# STorM32_NT_imu_v211_mini-mpu9250.net
KiCad netlist of a schematic drawn in EAGLE
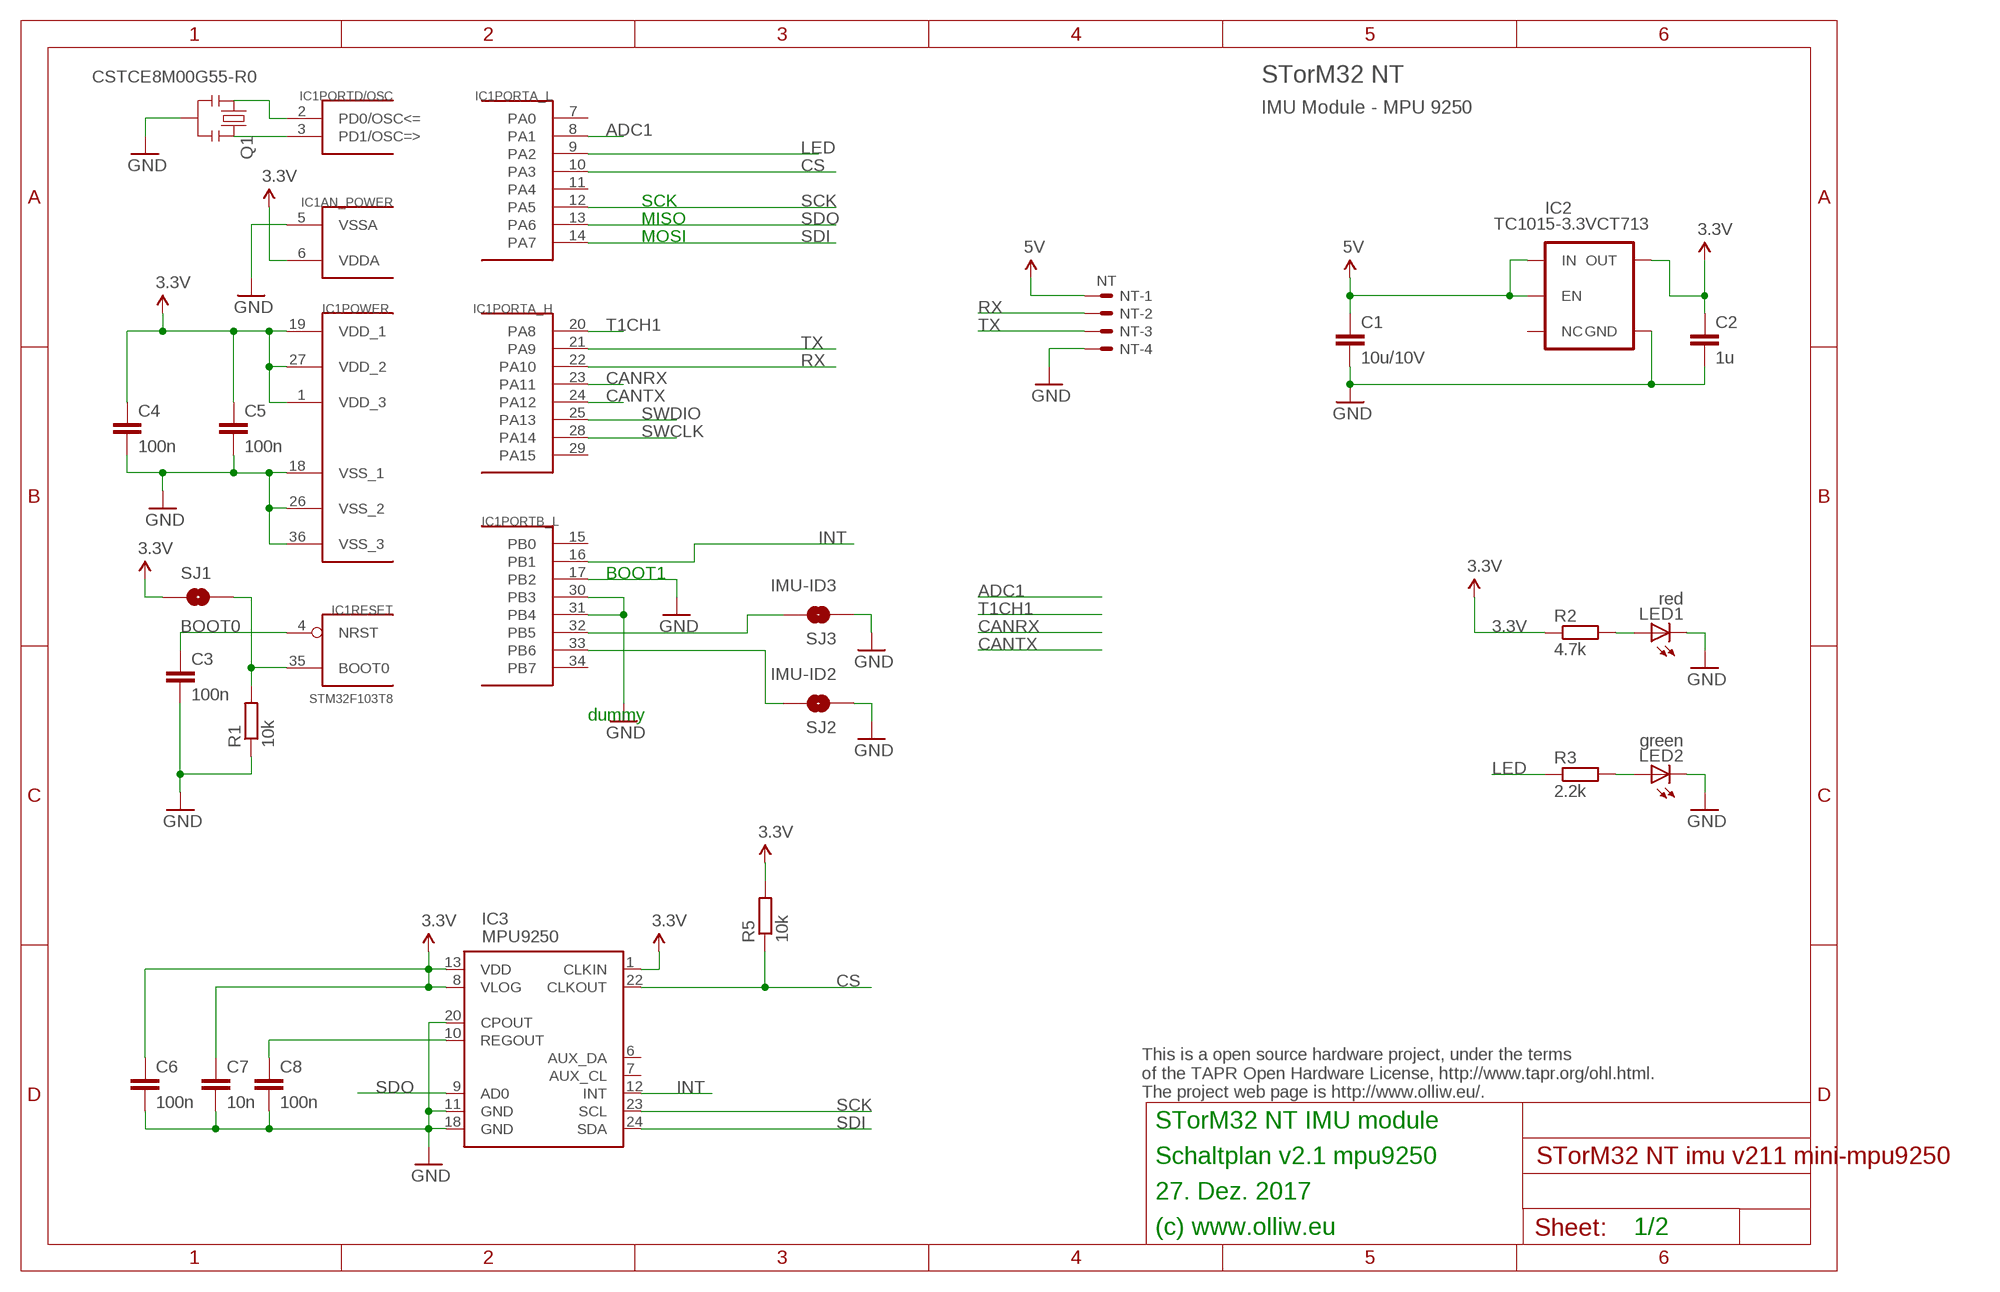
[diagram p0: schematic, sheet 1]

(export (version "E")
  (design (tool "Eeschema 10.0.6"))
  (components
    (comp (ref "C1")
      (value "10u/10V")
      (footprint "eagle-import:C0805")
      (libsource (lib "eagle-import") (part "C-EUC0805"))
    )
    (comp (ref "C2")
      (value "1u")
      (footprint "eagle-import:C0603")
      (libsource (lib "eagle-import") (part "C-EUC0603"))
    )
    (comp (ref "C3")
      (value "100n")
      (footprint "eagle-import:C0402")
      (libsource (lib "eagle-import") (part "C-EUC0402"))
    )
    (comp (ref "C4")
      (value "100n")
      (footprint "eagle-import:C0402")
      (libsource (lib "eagle-import") (part "C-EUC0402"))
    )
    (comp (ref "C5")
      (value "100n")
      (footprint "eagle-import:C0402")
      (libsource (lib "eagle-import") (part "C-EUC0402"))
    )
    (comp (ref "C6")
      (value "100n")
      (footprint "eagle-import:C0402")
      (libsource (lib "eagle-import") (part "C-EUC0402"))
    )
    (comp (ref "C7")
      (value "10n")
      (footprint "eagle-import:C0402")
      (libsource (lib "eagle-import") (part "C-EUC0402"))
    )
    (comp (ref "C8")
      (value "100n")
      (footprint "eagle-import:C0402")
      (libsource (lib "eagle-import") (part "C-EUC0402"))
    )
    (comp (ref "IC1")
      (value "STM32F103T8")
      (footprint "eagle-import:VFQFPN36")
      (libsource (lib "eagle-import") (part "STM32F10XTXU6"))
    )
    (comp (ref "IC2")
      (value "TC1015-3.3VCT713")
      (footprint "eagle-import:SOT23-5")
      (libsource (lib "eagle-import") (part "V_REG_TPS76433SOT23-5"))
    )
    (comp (ref "IC3")
      (value "MPU9250")
      (footprint "eagle-import:QFN-24-3X3")
      (libsource (lib "eagle-import") (part "IMU3000QFN-24-0.4MIL"))
    )
    (comp (ref "LED1")
      (value "red")
      (footprint "eagle-import:CHIPLED_0603")
      (libsource (lib "eagle-import") (part "LEDCHIPLED_0603"))
    )
    (comp (ref "LED2")
      (value "green")
      (footprint "eagle-import:CHIPLED_0603")
      (libsource (lib "eagle-import") (part "LEDCHIPLED_0603"))
    )
    (comp (ref "NT")
      (value "NT")
      (footprint "eagle-import:SM04B-SRSS-TB")
      (libsource (lib "eagle-import") (part "?M04B-SRSS-TBS"))
    )
    (comp (ref "Q1")
      (value "CSTCE8M00G55-R0")
      (footprint "eagle-import:RESONATOR-SMD")
      (libsource (lib "eagle-import") (part "RESONATORSMD"))
    )
    (comp (ref "R1")
      (value "10k")
      (footprint "eagle-import:R0402")
      (libsource (lib "eagle-import") (part "R-EU_R0402"))
    )
    (comp (ref "R2")
      (value "4.7k")
      (footprint "eagle-import:R0402")
      (libsource (lib "eagle-import") (part "R-EU_R0402"))
    )
    (comp (ref "R3")
      (value "2.2k")
      (footprint "eagle-import:R0402")
      (libsource (lib "eagle-import") (part "R-EU_R0402"))
    )
    (comp (ref "R5")
      (value "10k")
      (footprint "eagle-import:R0402")
      (libsource (lib "eagle-import") (part "R-EU_R0402"))
    )
    (comp (ref "SJ1")
      (value "BOOT0")
      (footprint "eagle-import:SJ_2S-NO")
      (libsource (lib "eagle-import") (part "SOLDERJUMPERNO"))
    )
    (comp (ref "SJ2")
      (value "IMU-ID2")
      (footprint "eagle-import:SJ_2S-NO")
      (libsource (lib "eagle-import") (part "SOLDERJUMPERNO"))
    )
    (comp (ref "SJ3")
      (value "IMU-ID3")
      (footprint "eagle-import:SJ_2S-NO")
      (libsource (lib "eagle-import") (part "SOLDERJUMPERNO"))
    )
  )
  (nets
    (net (code "1") (name "/ADC1") (class "Default")
      (node (ref "IC1") (pin "8") (pinfunction "PA1_8") (pintype "bidirectional"))
    )
    (net (code "2") (name "/CANRX") (class "Default")
      (node (ref "IC1") (pin "23") (pinfunction "PA11_23") (pintype "bidirectional"))
    )
    (net (code "3") (name "/CANTX") (class "Default")
      (node (ref "IC1") (pin "24") (pinfunction "PA12_24") (pintype "bidirectional"))
    )
    (net (code "4") (name "/CS") (class "Default")
      (node (ref "IC1") (pin "10") (pinfunction "PA3_10") (pintype "bidirectional"))
      (node (ref "IC3") (pin "22") (pinfunction "CLKOUT_22") (pintype "bidirectional"))
      (node (ref "R5") (pin "1") (pinfunction "1_1") (pintype "passive"))
    )
    (net (code "5") (name "/INT") (class "Default")
      (node (ref "IC1") (pin "16") (pinfunction "PB1_16") (pintype "bidirectional"))
      (node (ref "IC3") (pin "12") (pinfunction "INT_12") (pintype "bidirectional"))
    )
    (net (code "6") (name "/LED") (class "Default")
      (node (ref "IC1") (pin "9") (pinfunction "PA2_9") (pintype "bidirectional"))
      (node (ref "R3") (pin "1") (pinfunction "1_1") (pintype "passive"))
    )
    (net (code "7") (name "/RX") (class "Default")
      (node (ref "IC1") (pin "22") (pinfunction "PA10_22") (pintype "bidirectional"))
      (node (ref "NT") (pin "2") (pinfunction "S_2") (pintype "passive"))
    )
    (net (code "8") (name "/SCK") (class "Default")
      (node (ref "IC1") (pin "12") (pinfunction "PA5_12") (pintype "bidirectional"))
      (node (ref "IC3") (pin "23") (pinfunction "SCL_23") (pintype "bidirectional"))
    )
    (net (code "9") (name "/SDI") (class "Default")
      (node (ref "IC1") (pin "14") (pinfunction "PA7_14") (pintype "bidirectional"))
      (node (ref "IC3") (pin "24") (pinfunction "SDA_24") (pintype "bidirectional"))
    )
    (net (code "10") (name "/SDO") (class "Default")
      (node (ref "IC1") (pin "13") (pinfunction "PA6_13") (pintype "bidirectional"))
      (node (ref "IC3") (pin "9") (pinfunction "AD0_9") (pintype "bidirectional"))
    )
    (net (code "11") (name "/SWCLK") (class "Default")
      (node (ref "IC1") (pin "28") (pinfunction "PA14_28") (pintype "bidirectional"))
    )
    (net (code "12") (name "/SWDIO") (class "Default")
      (node (ref "IC1") (pin "25") (pinfunction "PA13_25") (pintype "bidirectional"))
    )
    (net (code "13") (name "/T1CH1") (class "Default")
      (node (ref "IC1") (pin "20") (pinfunction "PA8_20") (pintype "bidirectional"))
    )
    (net (code "14") (name "/TX") (class "Default")
      (node (ref "IC1") (pin "21") (pinfunction "PA9_21") (pintype "bidirectional"))
      (node (ref "NT") (pin "3") (pinfunction "S_3") (pintype "passive"))
    )
    (net (code "15") (name "3.3V") (class "Default")
      (node (ref "C2") (pin "1") (pinfunction "1_1") (pintype "passive"))
      (node (ref "C4") (pin "1") (pinfunction "1_1") (pintype "passive"))
      (node (ref "C5") (pin "1") (pinfunction "1_1") (pintype "passive"))
      (node (ref "C6") (pin "1") (pinfunction "1_1") (pintype "passive"))
      (node (ref "C7") (pin "1") (pinfunction "1_1") (pintype "passive"))
      (node (ref "IC1") (pin "1") (pinfunction "VDD_3_1") (pintype "power_in"))
      (node (ref "IC1") (pin "19") (pinfunction "VDD_1_19") (pintype "power_in"))
      (node (ref "IC1") (pin "27") (pinfunction "VDD_2_27") (pintype "power_in"))
      (node (ref "IC1") (pin "6") (pinfunction "VDDA_6") (pintype "power_in"))
      (node (ref "IC2") (pin "5") (pinfunction "OUT_5") (pintype "passive"))
      (node (ref "IC3") (pin "1") (pinfunction "CLKIN_1") (pintype "bidirectional"))
      (node (ref "IC3") (pin "13") (pinfunction "VDD_13") (pintype "bidirectional"))
      (node (ref "IC3") (pin "8") (pinfunction "VLOG_8") (pintype "bidirectional"))
      (node (ref "R2") (pin "1") (pinfunction "1_1") (pintype "passive"))
      (node (ref "R5") (pin "2") (pinfunction "2_2") (pintype "passive"))
      (node (ref "SJ1") (pin "1") (pinfunction "1_1") (pintype "passive"))
    )
    (net (code "16") (name "5V") (class "Default")
      (node (ref "C1") (pin "1") (pinfunction "1_1") (pintype "passive"))
      (node (ref "IC2") (pin "1") (pinfunction "IN_1") (pintype "input"))
      (node (ref "IC2") (pin "3") (pinfunction "EN_3") (pintype "input"))
      (node (ref "NT") (pin "1") (pinfunction "S_1") (pintype "passive"))
    )
    (net (code "17") (name "GND") (class "Default")
      (node (ref "C1") (pin "2") (pinfunction "2_2") (pintype "passive"))
      (node (ref "C2") (pin "2") (pinfunction "2_2") (pintype "passive"))
      (node (ref "C3") (pin "2") (pinfunction "2_2") (pintype "passive"))
      (node (ref "C4") (pin "2") (pinfunction "2_2") (pintype "passive"))
      (node (ref "C5") (pin "2") (pinfunction "2_2") (pintype "passive"))
      (node (ref "C6") (pin "2") (pinfunction "2_2") (pintype "passive"))
      (node (ref "C7") (pin "2") (pinfunction "2_2") (pintype "passive"))
      (node (ref "C8") (pin "2") (pinfunction "2_2") (pintype "passive"))
      (node (ref "IC1") (pin "17") (pinfunction "PB2_17") (pintype "bidirectional"))
      (node (ref "IC1") (pin "18") (pinfunction "VSS_1_18") (pintype "power_in"))
      (node (ref "IC1") (pin "26") (pinfunction "VSS_2_26") (pintype "power_in"))
      (node (ref "IC1") (pin "30") (pinfunction "PB3_30") (pintype "bidirectional"))
      (node (ref "IC1") (pin "31") (pinfunction "PB4_31") (pintype "bidirectional"))
      (node (ref "IC1") (pin "36") (pinfunction "VSS_3_36") (pintype "power_in"))
      (node (ref "IC1") (pin "5") (pinfunction "VSSA_5") (pintype "power_in"))
      (node (ref "IC2") (pin "2") (pinfunction "GND_2") (pintype "input"))
      (node (ref "IC3") (pin "11") (pinfunction "GND_11") (pintype "bidirectional"))
      (node (ref "IC3") (pin "18") (pinfunction "GND_18") (pintype "bidirectional"))
      (node (ref "IC3") (pin "20") (pinfunction "CPOUT_20") (pintype "bidirectional"))
      (node (ref "LED1") (pin "C") (pinfunction "C_C") (pintype "passive"))
      (node (ref "LED2") (pin "C") (pinfunction "C_C") (pintype "passive"))
      (node (ref "NT") (pin "4") (pinfunction "S_4") (pintype "passive"))
      (node (ref "Q1") (pin "2") (pinfunction "2_2") (pintype "passive"))
      (node (ref "R1") (pin "1") (pinfunction "1_1") (pintype "passive"))
      (node (ref "SJ2") (pin "1") (pinfunction "1_1") (pintype "passive"))
      (node (ref "SJ3") (pin "1") (pinfunction "1_1") (pintype "passive"))
    )
    (net (code "18") (name "Net-(IC1D-PB5)") (class "Default")
      (node (ref "IC1") (pin "32") (pinfunction "PB5_32") (pintype "bidirectional"))
      (node (ref "SJ3") (pin "2") (pinfunction "2_2") (pintype "passive"))
    )
    (net (code "19") (name "Net-(IC1D-PB6)") (class "Default")
      (node (ref "IC1") (pin "33") (pinfunction "PB6_33") (pintype "bidirectional"))
      (node (ref "SJ2") (pin "2") (pinfunction "2_2") (pintype "passive"))
    )
    (net (code "20") (name "Net-(IC1E-PD0{slash}OSC<=)") (class "Default")
      (node (ref "IC1") (pin "2") (pinfunction "PD0/OSC<=_2") (pintype "bidirectional"))
      (node (ref "Q1") (pin "1") (pinfunction "1_1") (pintype "passive"))
    )
    (net (code "21") (name "Net-(IC1E-PD1{slash}OSC=>)") (class "Default")
      (node (ref "IC1") (pin "3") (pinfunction "PD1/OSC=>_3") (pintype "bidirectional"))
      (node (ref "Q1") (pin "3") (pinfunction "3_3") (pintype "passive"))
    )
    (net (code "22") (name "Net-(IC1G-BOOT0)") (class "Default")
      (node (ref "IC1") (pin "35") (pinfunction "BOOT0_35") (pintype "input"))
      (node (ref "R1") (pin "2") (pinfunction "2_2") (pintype "passive"))
      (node (ref "SJ1") (pin "2") (pinfunction "2_2") (pintype "passive"))
    )
    (net (code "23") (name "Net-(IC1G-NRST)") (class "Default")
      (node (ref "C3") (pin "1") (pinfunction "1_1") (pintype "passive"))
      (node (ref "IC1") (pin "4") (pinfunction "NRST_4") (pintype "input"))
    )
    (net (code "24") (name "Net-(IC3-REGOUT)") (class "Default")
      (node (ref "C8") (pin "1") (pinfunction "1_1") (pintype "passive"))
      (node (ref "IC3") (pin "10") (pinfunction "REGOUT_10") (pintype "bidirectional"))
    )
    (net (code "25") (name "Net-(LED1-PadA)") (class "Default")
      (node (ref "LED1") (pin "A") (pinfunction "A_A") (pintype "passive"))
      (node (ref "R2") (pin "2") (pinfunction "2_2") (pintype "passive"))
    )
    (net (code "26") (name "Net-(LED2-PadA)") (class "Default")
      (node (ref "LED2") (pin "A") (pinfunction "A_A") (pintype "passive"))
      (node (ref "R3") (pin "2") (pinfunction "2_2") (pintype "passive"))
    )
    (net (code "27") (name "unconnected-(IC1B-PA15-Pad29)") (class "Default")
      (node (ref "IC1") (pin "29") (pinfunction "PA15_29") (pintype "bidirectional"))
    )
    (net (code "28") (name "unconnected-(IC1C-PA0-Pad7)") (class "Default")
      (node (ref "IC1") (pin "7") (pinfunction "PA0_7") (pintype "bidirectional"))
    )
    (net (code "29") (name "unconnected-(IC1C-PA4-Pad11)") (class "Default")
      (node (ref "IC1") (pin "11") (pinfunction "PA4_11") (pintype "bidirectional"))
    )
    (net (code "30") (name "unconnected-(IC1D-PB0-Pad15)") (class "Default")
      (node (ref "IC1") (pin "15") (pinfunction "PB0_15") (pintype "bidirectional"))
    )
    (net (code "31") (name "unconnected-(IC1D-PB7-Pad34)") (class "Default")
      (node (ref "IC1") (pin "34") (pinfunction "PB7_34") (pintype "bidirectional"))
    )
    (net (code "32") (name "unconnected-(IC2-NC-Pad4)") (class "Default")
      (node (ref "IC2") (pin "4") (pinfunction "NC_4") (pintype "input"))
    )
    (net (code "33") (name "unconnected-(IC3-AUX_CL-Pad7)") (class "Default")
      (node (ref "IC3") (pin "7") (pinfunction "AUX_CL_7") (pintype "bidirectional"))
    )
    (net (code "34") (name "unconnected-(IC3-AUX_DA-Pad6)") (class "Default")
      (node (ref "IC3") (pin "6") (pinfunction "AUX_DA_6") (pintype "bidirectional"))
    )
  )
)
